# VIC20_SExpII.net
KiCad netlist of a schematic drawn in EAGLE
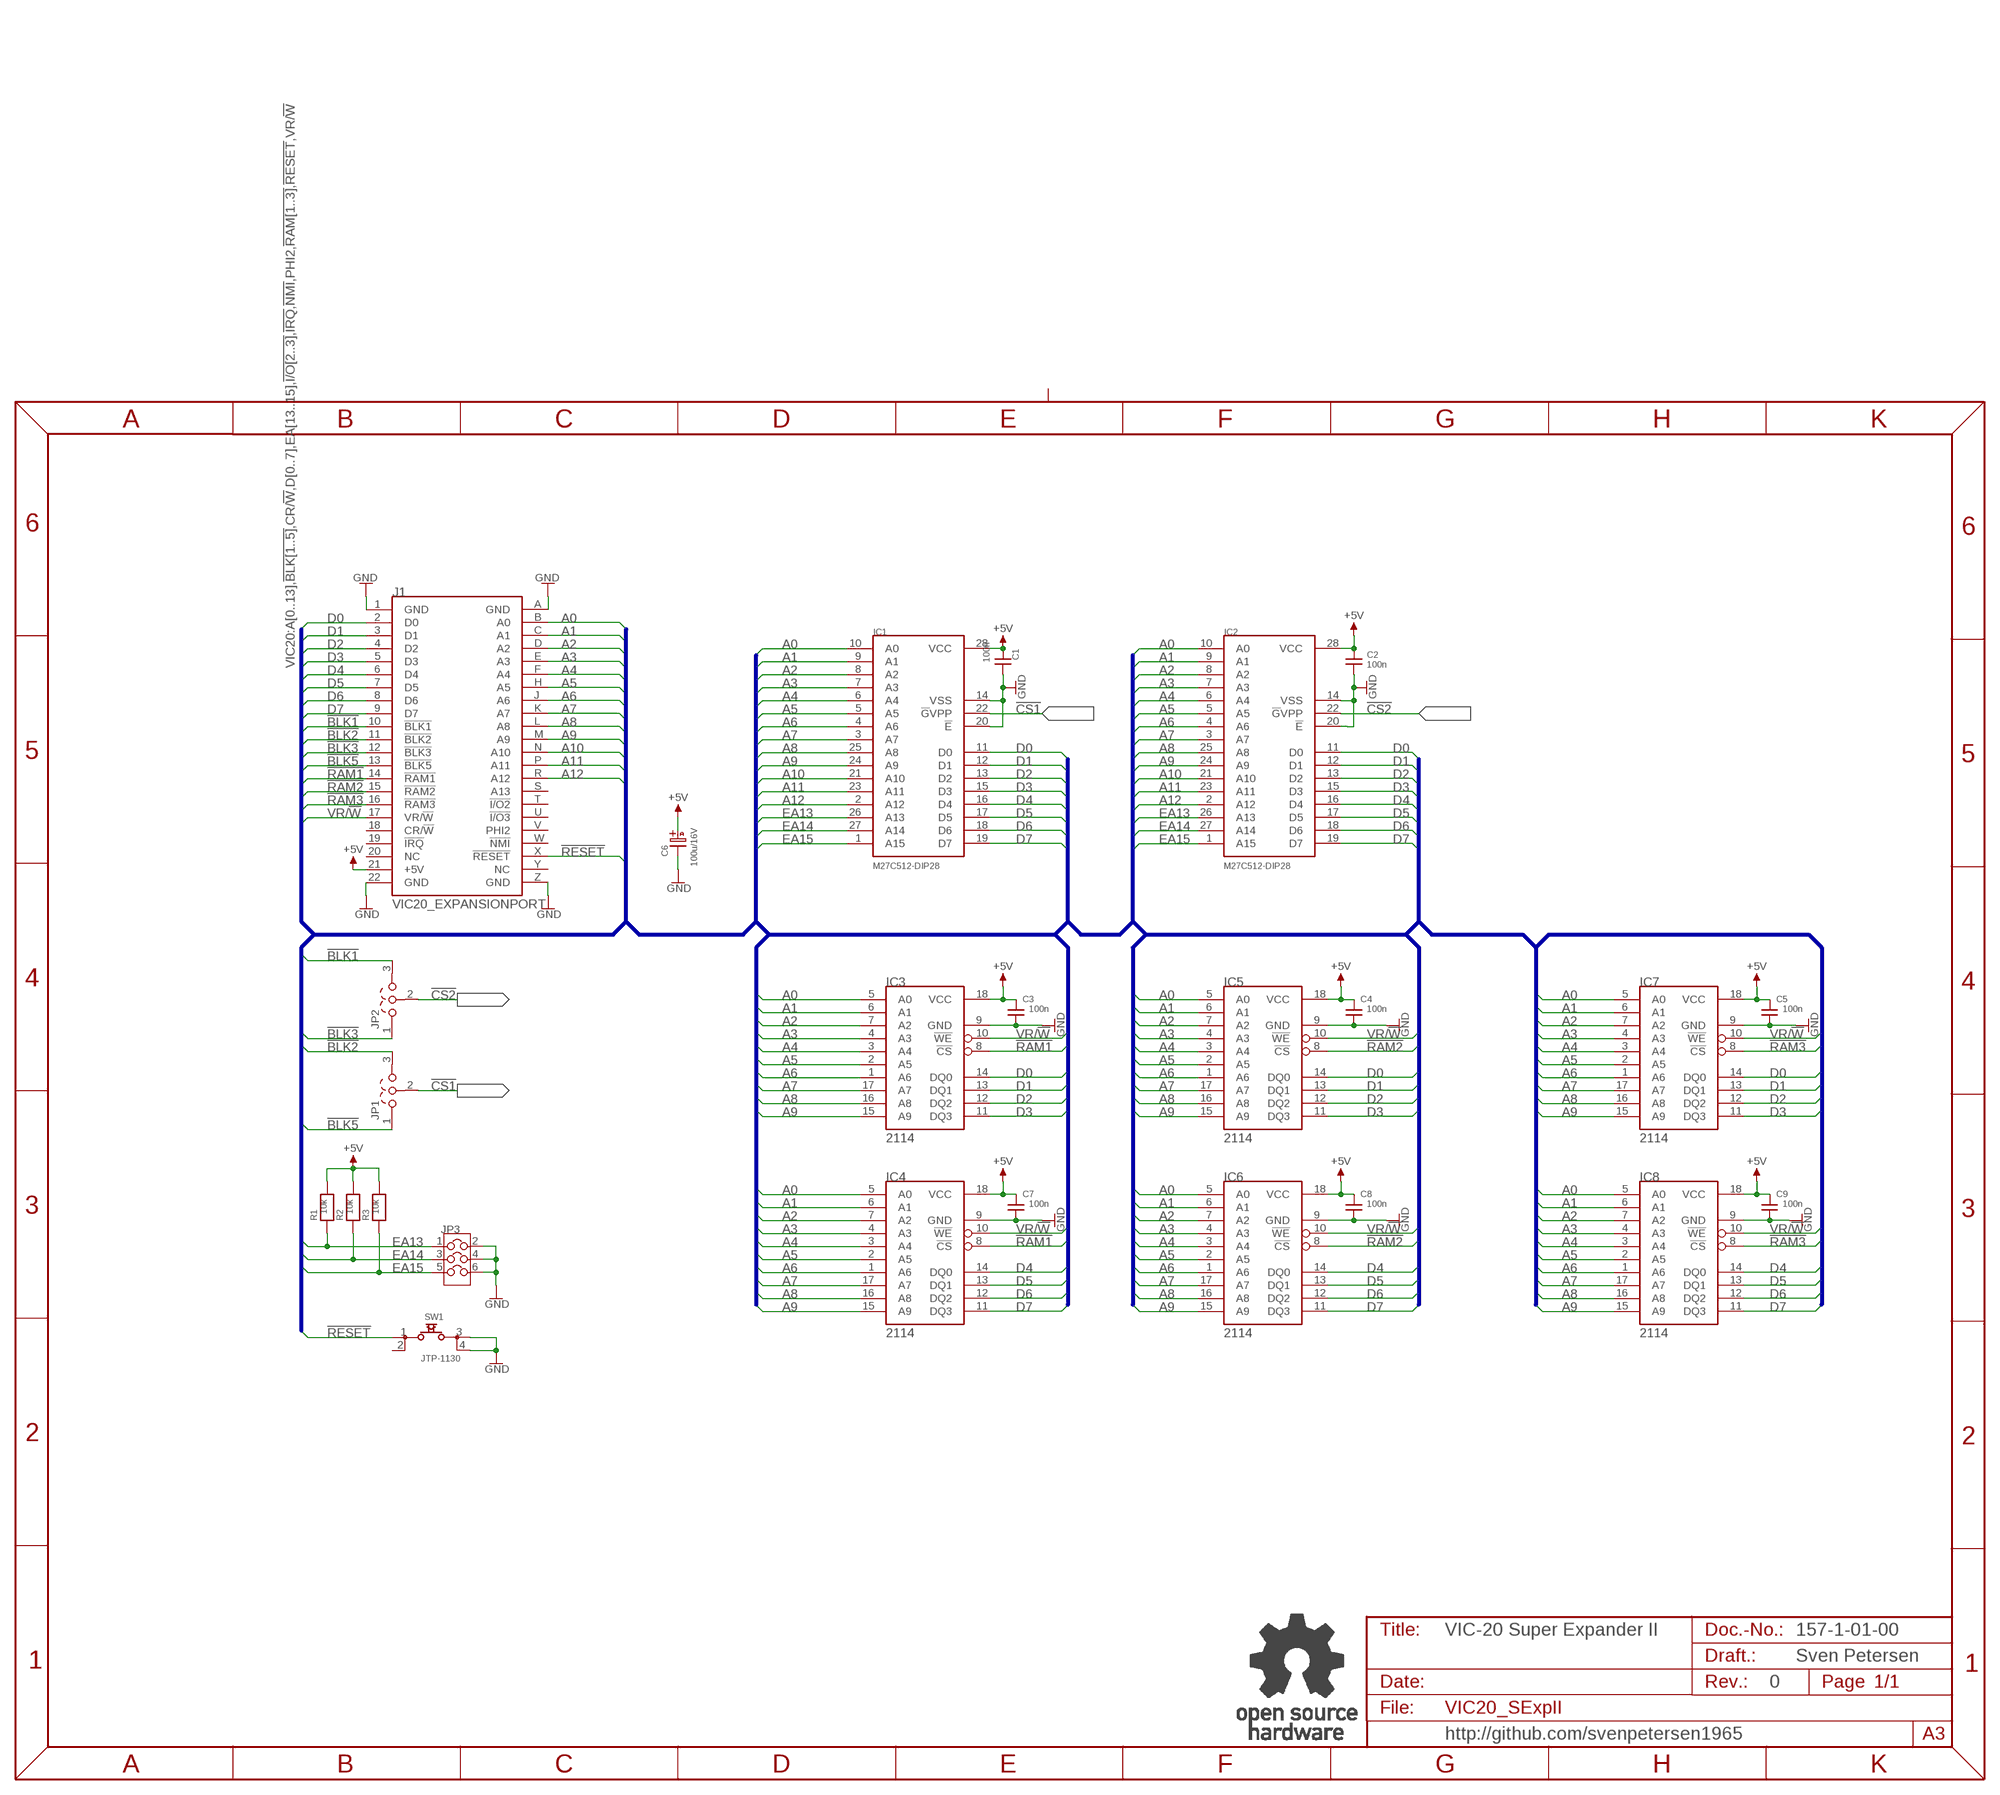
[diagram p0: schematic, sheet 1]

(export (version "E")
  (design (tool "Eeschema 10.0.6"))
  (components
    (comp (ref "C1")
      (value "100n")
      (footprint "eagle-import:C-2,5")
      (libsource (lib "eagle-import") (part "CAP01"))
    )
    (comp (ref "C2")
      (value "100n")
      (footprint "eagle-import:C-2,5")
      (libsource (lib "eagle-import") (part "CAP01"))
    )
    (comp (ref "C3")
      (value "100n")
      (footprint "eagle-import:C-2,5")
      (libsource (lib "eagle-import") (part "CAP01"))
    )
    (comp (ref "C4")
      (value "100n")
      (footprint "eagle-import:C-2,5")
      (libsource (lib "eagle-import") (part "CAP01"))
    )
    (comp (ref "C5")
      (value "100n")
      (footprint "eagle-import:C-2,5")
      (libsource (lib "eagle-import") (part "CAP01"))
    )
    (comp (ref "C6")
      (value "100u/16V")
      (footprint "eagle-import:C07_2,5")
      (libsource (lib "eagle-import") (part "C07/2,5"))
    )
    (comp (ref "C7")
      (value "100n")
      (footprint "eagle-import:C-2,5")
      (libsource (lib "eagle-import") (part "CAP01"))
    )
    (comp (ref "C8")
      (value "100n")
      (footprint "eagle-import:C-2,5")
      (libsource (lib "eagle-import") (part "CAP01"))
    )
    (comp (ref "C9")
      (value "100n")
      (footprint "eagle-import:C-2,5")
      (libsource (lib "eagle-import") (part "CAP01"))
    )
    (comp (ref "IC1")
      (value "M27C512-DIP28")
      (footprint "eagle-import:DIL28-6")
      (libsource (lib "eagle-import") (part "M27C512-DIP28"))
    )
    (comp (ref "IC2")
      (value "M27C512-DIP28")
      (footprint "eagle-import:DIL28-6")
      (libsource (lib "eagle-import") (part "M27C512-DIP28"))
    )
    (comp (ref "IC3")
      (value "2114")
      (footprint "eagle-import:DIL18")
      (libsource (lib "eagle-import") (part "2114"))
    )
    (comp (ref "IC4")
      (value "2114")
      (footprint "eagle-import:DIL18")
      (libsource (lib "eagle-import") (part "2114"))
    )
    (comp (ref "IC5")
      (value "2114")
      (footprint "eagle-import:DIL18")
      (libsource (lib "eagle-import") (part "2114"))
    )
    (comp (ref "IC6")
      (value "2114")
      (footprint "eagle-import:DIL18")
      (libsource (lib "eagle-import") (part "2114"))
    )
    (comp (ref "IC7")
      (value "2114")
      (footprint "eagle-import:DIL18")
      (libsource (lib "eagle-import") (part "2114"))
    )
    (comp (ref "IC8")
      (value "2114")
      (footprint "eagle-import:DIL18")
      (libsource (lib "eagle-import") (part "2114"))
    )
    (comp (ref "J1")
      (value "VIC20_EXPANSIONPORT")
      (footprint "eagle-import:VIC20_EXPANSION")
      (libsource (lib "eagle-import") (part "VIC20_EXPANSIONPORT"))
    )
    (comp (ref "JP1")
      (value "COMBI-3P")
      (footprint "eagle-import:COMBI-3P")
      (libsource (lib "eagle-import") (part "COMBI-3P"))
    )
    (comp (ref "JP2")
      (value "COMBI-3P")
      (footprint "eagle-import:COMBI-3P")
      (libsource (lib "eagle-import") (part "COMBI-3P"))
    )
    (comp (ref "JP3")
      (value "COMBI-3X2P")
      (footprint "eagle-import:COMBI-3X2")
      (libsource (lib "eagle-import") (part "COMBI-3X2P"))
    )
    (comp (ref "R1")
      (value "10k")
      (footprint "eagle-import:R-10")
      (libsource (lib "eagle-import") (part "RES04"))
    )
    (comp (ref "R2")
      (value "10k")
      (footprint "eagle-import:R-10")
      (libsource (lib "eagle-import") (part "RES04"))
    )
    (comp (ref "R3")
      (value "10k")
      (footprint "eagle-import:R-10")
      (libsource (lib "eagle-import") (part "RES04"))
    )
    (comp (ref "SW1")
      (value "JTP-1130")
      (footprint "eagle-import:JTP-1130")
      (libsource (lib "eagle-import") (part "JTP-1130"))
    )
    (comp (ref "U$2")
      (value "OPEN_SOURCE_HW")
      (footprint "eagle-import:OPENHW")
      (libsource (lib "eagle-import") (part "OPEN_SOURCE_HW"))
    )
  )
  (nets
    (net (code "5") (name "+5V") (class "Default")
      (node (ref "C1") (pin "1") (pinfunction "1_1") (pintype "passive"))
      (node (ref "C2") (pin "1") (pinfunction "1_1") (pintype "passive"))
      (node (ref "C3") (pin "2") (pinfunction "2_2") (pintype "passive"))
      (node (ref "C4") (pin "2") (pinfunction "2_2") (pintype "passive"))
      (node (ref "C5") (pin "2") (pinfunction "2_2") (pintype "passive"))
      (node (ref "C6") (pin "A") (pinfunction "+_A") (pintype "passive"))
      (node (ref "C7") (pin "2") (pinfunction "2_2") (pintype "passive"))
      (node (ref "C8") (pin "2") (pinfunction "2_2") (pintype "passive"))
      (node (ref "C9") (pin "2") (pinfunction "2_2") (pintype "passive"))
      (node (ref "IC1") (pin "28") (pinfunction "VCC_28") (pintype "power_in"))
      (node (ref "IC2") (pin "28") (pinfunction "VCC_28") (pintype "power_in"))
      (node (ref "IC3") (pin "18") (pinfunction "VCC_18") (pintype "power_in"))
      (node (ref "IC4") (pin "18") (pinfunction "VCC_18") (pintype "power_in"))
      (node (ref "IC5") (pin "18") (pinfunction "VCC_18") (pintype "power_in"))
      (node (ref "IC6") (pin "18") (pinfunction "VCC_18") (pintype "power_in"))
      (node (ref "IC7") (pin "18") (pinfunction "VCC_18") (pintype "power_in"))
      (node (ref "IC8") (pin "18") (pinfunction "VCC_18") (pintype "power_in"))
      (node (ref "J1") (pin "21") (pinfunction "+5V_21") (pintype "power_in"))
      (node (ref "R1") (pin "2") (pinfunction "2_2") (pintype "passive"))
      (node (ref "R2") (pin "2") (pinfunction "2_2") (pintype "passive"))
      (node (ref "R3") (pin "2") (pinfunction "2_2") (pintype "passive"))
    )
    (net (code "6") (name "/A0") (class "Default")
      (node (ref "IC1") (pin "10") (pinfunction "A0_10") (pintype "input"))
      (node (ref "IC2") (pin "10") (pinfunction "A0_10") (pintype "input"))
      (node (ref "IC3") (pin "5") (pinfunction "A0_5") (pintype "input"))
      (node (ref "IC4") (pin "5") (pinfunction "A0_5") (pintype "input"))
      (node (ref "IC5") (pin "5") (pinfunction "A0_5") (pintype "input"))
      (node (ref "IC6") (pin "5") (pinfunction "A0_5") (pintype "input"))
      (node (ref "IC7") (pin "5") (pinfunction "A0_5") (pintype "input"))
      (node (ref "IC8") (pin "5") (pinfunction "A0_5") (pintype "input"))
      (node (ref "J1") (pin "B") (pinfunction "A0_B") (pintype "bidirectional"))
    )
    (net (code "7") (name "/A1") (class "Default")
      (node (ref "IC1") (pin "9") (pinfunction "A1_9") (pintype "input"))
      (node (ref "IC2") (pin "9") (pinfunction "A1_9") (pintype "input"))
      (node (ref "IC3") (pin "6") (pinfunction "A1_6") (pintype "input"))
      (node (ref "IC4") (pin "6") (pinfunction "A1_6") (pintype "input"))
      (node (ref "IC5") (pin "6") (pinfunction "A1_6") (pintype "input"))
      (node (ref "IC6") (pin "6") (pinfunction "A1_6") (pintype "input"))
      (node (ref "IC7") (pin "6") (pinfunction "A1_6") (pintype "input"))
      (node (ref "IC8") (pin "6") (pinfunction "A1_6") (pintype "input"))
      (node (ref "J1") (pin "C") (pinfunction "A1_C") (pintype "bidirectional"))
    )
    (net (code "8") (name "/A2") (class "Default")
      (node (ref "IC1") (pin "8") (pinfunction "A2_8") (pintype "input"))
      (node (ref "IC2") (pin "8") (pinfunction "A2_8") (pintype "input"))
      (node (ref "IC3") (pin "7") (pinfunction "A2_7") (pintype "input"))
      (node (ref "IC4") (pin "7") (pinfunction "A2_7") (pintype "input"))
      (node (ref "IC5") (pin "7") (pinfunction "A2_7") (pintype "input"))
      (node (ref "IC6") (pin "7") (pinfunction "A2_7") (pintype "input"))
      (node (ref "IC7") (pin "7") (pinfunction "A2_7") (pintype "input"))
      (node (ref "IC8") (pin "7") (pinfunction "A2_7") (pintype "input"))
      (node (ref "J1") (pin "D") (pinfunction "A2_D") (pintype "bidirectional"))
    )
    (net (code "9") (name "/A3") (class "Default")
      (node (ref "IC1") (pin "7") (pinfunction "A3_7") (pintype "input"))
      (node (ref "IC2") (pin "7") (pinfunction "A3_7") (pintype "input"))
      (node (ref "IC3") (pin "4") (pinfunction "A3_4") (pintype "input"))
      (node (ref "IC4") (pin "4") (pinfunction "A3_4") (pintype "input"))
      (node (ref "IC5") (pin "4") (pinfunction "A3_4") (pintype "input"))
      (node (ref "IC6") (pin "4") (pinfunction "A3_4") (pintype "input"))
      (node (ref "IC7") (pin "4") (pinfunction "A3_4") (pintype "input"))
      (node (ref "IC8") (pin "4") (pinfunction "A3_4") (pintype "input"))
      (node (ref "J1") (pin "E") (pinfunction "A3_E") (pintype "bidirectional"))
    )
    (net (code "10") (name "/A4") (class "Default")
      (node (ref "IC1") (pin "6") (pinfunction "A4_6") (pintype "input"))
      (node (ref "IC2") (pin "6") (pinfunction "A4_6") (pintype "input"))
      (node (ref "IC3") (pin "3") (pinfunction "A4_3") (pintype "input"))
      (node (ref "IC4") (pin "3") (pinfunction "A4_3") (pintype "input"))
      (node (ref "IC5") (pin "3") (pinfunction "A4_3") (pintype "input"))
      (node (ref "IC6") (pin "3") (pinfunction "A4_3") (pintype "input"))
      (node (ref "IC7") (pin "3") (pinfunction "A4_3") (pintype "input"))
      (node (ref "IC8") (pin "3") (pinfunction "A4_3") (pintype "input"))
      (node (ref "J1") (pin "F") (pinfunction "A4_F") (pintype "bidirectional"))
    )
    (net (code "11") (name "/A5") (class "Default")
      (node (ref "IC1") (pin "5") (pinfunction "A5_5") (pintype "input"))
      (node (ref "IC2") (pin "5") (pinfunction "A5_5") (pintype "input"))
      (node (ref "IC3") (pin "2") (pinfunction "A5_2") (pintype "input"))
      (node (ref "IC4") (pin "2") (pinfunction "A5_2") (pintype "input"))
      (node (ref "IC5") (pin "2") (pinfunction "A5_2") (pintype "input"))
      (node (ref "IC6") (pin "2") (pinfunction "A5_2") (pintype "input"))
      (node (ref "IC7") (pin "2") (pinfunction "A5_2") (pintype "input"))
      (node (ref "IC8") (pin "2") (pinfunction "A5_2") (pintype "input"))
      (node (ref "J1") (pin "H") (pinfunction "A5_H") (pintype "bidirectional"))
    )
    (net (code "12") (name "/A6") (class "Default")
      (node (ref "IC1") (pin "4") (pinfunction "A6_4") (pintype "input"))
      (node (ref "IC2") (pin "4") (pinfunction "A6_4") (pintype "input"))
      (node (ref "IC3") (pin "1") (pinfunction "A6_1") (pintype "input"))
      (node (ref "IC4") (pin "1") (pinfunction "A6_1") (pintype "input"))
      (node (ref "IC5") (pin "1") (pinfunction "A6_1") (pintype "input"))
      (node (ref "IC6") (pin "1") (pinfunction "A6_1") (pintype "input"))
      (node (ref "IC7") (pin "1") (pinfunction "A6_1") (pintype "input"))
      (node (ref "IC8") (pin "1") (pinfunction "A6_1") (pintype "input"))
      (node (ref "J1") (pin "J") (pinfunction "A6_J") (pintype "bidirectional"))
    )
    (net (code "13") (name "/A7") (class "Default")
      (node (ref "IC1") (pin "3") (pinfunction "A7_3") (pintype "input"))
      (node (ref "IC2") (pin "3") (pinfunction "A7_3") (pintype "input"))
      (node (ref "IC3") (pin "17") (pinfunction "A7_17") (pintype "input"))
      (node (ref "IC4") (pin "17") (pinfunction "A7_17") (pintype "input"))
      (node (ref "IC5") (pin "17") (pinfunction "A7_17") (pintype "input"))
      (node (ref "IC6") (pin "17") (pinfunction "A7_17") (pintype "input"))
      (node (ref "IC7") (pin "17") (pinfunction "A7_17") (pintype "input"))
      (node (ref "IC8") (pin "17") (pinfunction "A7_17") (pintype "input"))
      (node (ref "J1") (pin "K") (pinfunction "A7_K") (pintype "bidirectional"))
    )
    (net (code "14") (name "/A8") (class "Default")
      (node (ref "IC1") (pin "25") (pinfunction "A8_25") (pintype "input"))
      (node (ref "IC2") (pin "25") (pinfunction "A8_25") (pintype "input"))
      (node (ref "IC3") (pin "16") (pinfunction "A8_16") (pintype "input"))
      (node (ref "IC4") (pin "16") (pinfunction "A8_16") (pintype "input"))
      (node (ref "IC5") (pin "16") (pinfunction "A8_16") (pintype "input"))
      (node (ref "IC6") (pin "16") (pinfunction "A8_16") (pintype "input"))
      (node (ref "IC7") (pin "16") (pinfunction "A8_16") (pintype "input"))
      (node (ref "IC8") (pin "16") (pinfunction "A8_16") (pintype "input"))
      (node (ref "J1") (pin "L") (pinfunction "A8_L") (pintype "bidirectional"))
    )
    (net (code "15") (name "/A9") (class "Default")
      (node (ref "IC1") (pin "24") (pinfunction "A9_24") (pintype "input"))
      (node (ref "IC2") (pin "24") (pinfunction "A9_24") (pintype "input"))
      (node (ref "IC3") (pin "15") (pinfunction "A9_15") (pintype "input"))
      (node (ref "IC4") (pin "15") (pinfunction "A9_15") (pintype "input"))
      (node (ref "IC5") (pin "15") (pinfunction "A9_15") (pintype "input"))
      (node (ref "IC6") (pin "15") (pinfunction "A9_15") (pintype "input"))
      (node (ref "IC7") (pin "15") (pinfunction "A9_15") (pintype "input"))
      (node (ref "IC8") (pin "15") (pinfunction "A9_15") (pintype "input"))
      (node (ref "J1") (pin "M") (pinfunction "A9_M") (pintype "bidirectional"))
    )
    (net (code "16") (name "/A10") (class "Default")
      (node (ref "IC1") (pin "21") (pinfunction "A10_21") (pintype "input"))
      (node (ref "IC2") (pin "21") (pinfunction "A10_21") (pintype "input"))
      (node (ref "J1") (pin "N") (pinfunction "A10_N") (pintype "bidirectional"))
    )
    (net (code "17") (name "/A11") (class "Default")
      (node (ref "IC1") (pin "23") (pinfunction "A11_23") (pintype "input"))
      (node (ref "IC2") (pin "23") (pinfunction "A11_23") (pintype "input"))
      (node (ref "J1") (pin "P") (pinfunction "A11_P") (pintype "bidirectional"))
    )
    (net (code "18") (name "/A12") (class "Default")
      (node (ref "IC1") (pin "2") (pinfunction "A12_2") (pintype "input"))
      (node (ref "IC2") (pin "2") (pinfunction "A12_2") (pintype "input"))
      (node (ref "J1") (pin "R") (pinfunction "A12_R") (pintype "bidirectional"))
    )
    (net (code "19") (name "/D0") (class "Default")
      (node (ref "IC1") (pin "11") (pinfunction "D0_11") (pintype "bidirectional"))
      (node (ref "IC2") (pin "11") (pinfunction "D0_11") (pintype "bidirectional"))
      (node (ref "IC3") (pin "14") (pinfunction "DQ0_14") (pintype "bidirectional"))
      (node (ref "IC5") (pin "14") (pinfunction "DQ0_14") (pintype "bidirectional"))
      (node (ref "IC7") (pin "14") (pinfunction "DQ0_14") (pintype "bidirectional"))
      (node (ref "J1") (pin "2") (pinfunction "D0_2") (pintype "bidirectional"))
    )
    (net (code "20") (name "/D1") (class "Default")
      (node (ref "IC1") (pin "12") (pinfunction "D1_12") (pintype "bidirectional"))
      (node (ref "IC2") (pin "12") (pinfunction "D1_12") (pintype "bidirectional"))
      (node (ref "IC3") (pin "13") (pinfunction "DQ1_13") (pintype "bidirectional"))
      (node (ref "IC5") (pin "13") (pinfunction "DQ1_13") (pintype "bidirectional"))
      (node (ref "IC7") (pin "13") (pinfunction "DQ1_13") (pintype "bidirectional"))
      (node (ref "J1") (pin "3") (pinfunction "D1_3") (pintype "bidirectional"))
    )
    (net (code "21") (name "/D2") (class "Default")
      (node (ref "IC1") (pin "13") (pinfunction "D2_13") (pintype "bidirectional"))
      (node (ref "IC2") (pin "13") (pinfunction "D2_13") (pintype "bidirectional"))
      (node (ref "IC3") (pin "12") (pinfunction "DQ2_12") (pintype "bidirectional"))
      (node (ref "IC5") (pin "12") (pinfunction "DQ2_12") (pintype "bidirectional"))
      (node (ref "IC7") (pin "12") (pinfunction "DQ2_12") (pintype "bidirectional"))
      (node (ref "J1") (pin "4") (pinfunction "D2_4") (pintype "bidirectional"))
    )
    (net (code "22") (name "/D3") (class "Default")
      (node (ref "IC1") (pin "15") (pinfunction "D3_15") (pintype "bidirectional"))
      (node (ref "IC2") (pin "15") (pinfunction "D3_15") (pintype "bidirectional"))
      (node (ref "IC3") (pin "11") (pinfunction "DQ3_11") (pintype "bidirectional"))
      (node (ref "IC5") (pin "11") (pinfunction "DQ3_11") (pintype "bidirectional"))
      (node (ref "IC7") (pin "11") (pinfunction "DQ3_11") (pintype "bidirectional"))
      (node (ref "J1") (pin "5") (pinfunction "D3_5") (pintype "bidirectional"))
    )
    (net (code "23") (name "/D4") (class "Default")
      (node (ref "IC1") (pin "16") (pinfunction "D4_16") (pintype "bidirectional"))
      (node (ref "IC2") (pin "16") (pinfunction "D4_16") (pintype "bidirectional"))
      (node (ref "IC4") (pin "14") (pinfunction "DQ0_14") (pintype "bidirectional"))
      (node (ref "IC6") (pin "14") (pinfunction "DQ0_14") (pintype "bidirectional"))
      (node (ref "IC8") (pin "14") (pinfunction "DQ0_14") (pintype "bidirectional"))
      (node (ref "J1") (pin "6") (pinfunction "D4_6") (pintype "bidirectional"))
    )
    (net (code "24") (name "/D5") (class "Default")
      (node (ref "IC1") (pin "17") (pinfunction "D5_17") (pintype "bidirectional"))
      (node (ref "IC2") (pin "17") (pinfunction "D5_17") (pintype "bidirectional"))
      (node (ref "IC4") (pin "13") (pinfunction "DQ1_13") (pintype "bidirectional"))
      (node (ref "IC6") (pin "13") (pinfunction "DQ1_13") (pintype "bidirectional"))
      (node (ref "IC8") (pin "13") (pinfunction "DQ1_13") (pintype "bidirectional"))
      (node (ref "J1") (pin "7") (pinfunction "D5_7") (pintype "bidirectional"))
    )
    (net (code "25") (name "/D6") (class "Default")
      (node (ref "IC1") (pin "18") (pinfunction "D6_18") (pintype "bidirectional"))
      (node (ref "IC2") (pin "18") (pinfunction "D6_18") (pintype "bidirectional"))
      (node (ref "IC4") (pin "12") (pinfunction "DQ2_12") (pintype "bidirectional"))
      (node (ref "IC6") (pin "12") (pinfunction "DQ2_12") (pintype "bidirectional"))
      (node (ref "IC8") (pin "12") (pinfunction "DQ2_12") (pintype "bidirectional"))
      (node (ref "J1") (pin "8") (pinfunction "D6_8") (pintype "bidirectional"))
    )
    (net (code "26") (name "/D7") (class "Default")
      (node (ref "IC1") (pin "19") (pinfunction "D7_19") (pintype "bidirectional"))
      (node (ref "IC2") (pin "19") (pinfunction "D7_19") (pintype "bidirectional"))
      (node (ref "IC4") (pin "11") (pinfunction "DQ3_11") (pintype "bidirectional"))
      (node (ref "IC6") (pin "11") (pinfunction "DQ3_11") (pintype "bidirectional"))
      (node (ref "IC8") (pin "11") (pinfunction "DQ3_11") (pintype "bidirectional"))
      (node (ref "J1") (pin "9") (pinfunction "D7_9") (pintype "bidirectional"))
    )
    (net (code "27") (name "/EA13") (class "Default")
      (node (ref "IC1") (pin "26") (pinfunction "A13_26") (pintype "input"))
      (node (ref "IC2") (pin "26") (pinfunction "A13_26") (pintype "input"))
      (node (ref "JP3") (pin "1") (pinfunction "1_1") (pintype "bidirectional"))
      (node (ref "R1") (pin "1") (pinfunction "1_1") (pintype "passive"))
    )
    (net (code "28") (name "/EA14") (class "Default")
      (node (ref "IC1") (pin "27") (pinfunction "A14_27") (pintype "input"))
      (node (ref "IC2") (pin "27") (pinfunction "A14_27") (pintype "input"))
      (node (ref "JP3") (pin "3") (pinfunction "3_3") (pintype "bidirectional"))
      (node (ref "R2") (pin "1") (pinfunction "1_1") (pintype "passive"))
    )
    (net (code "29") (name "/EA15") (class "Default")
      (node (ref "IC1") (pin "1") (pinfunction "A15_1") (pintype "input"))
      (node (ref "IC2") (pin "1") (pinfunction "A15_1") (pintype "input"))
      (node (ref "JP3") (pin "5") (pinfunction "5_5") (pintype "bidirectional"))
      (node (ref "R3") (pin "1") (pinfunction "1_1") (pintype "passive"))
    )
    (net (code "30") (name "/NC") (class "Default")
      (node (ref "J1") (pin "20") (pinfunction "NC_20") (pintype "power_in"))
    )
    (net (code "31") (name "/VR{slash}~{W}") (class "Default")
      (node (ref "IC3") (pin "10") (pinfunction "~{WE}_10") (pintype "input"))
      (node (ref "IC4") (pin "10") (pinfunction "~{WE}_10") (pintype "input"))
      (node (ref "IC5") (pin "10") (pinfunction "~{WE}_10") (pintype "input"))
      (node (ref "IC6") (pin "10") (pinfunction "~{WE}_10") (pintype "input"))
      (node (ref "IC7") (pin "10") (pinfunction "~{WE}_10") (pintype "input"))
      (node (ref "IC8") (pin "10") (pinfunction "~{WE}_10") (pintype "input"))
      (node (ref "J1") (pin "17") (pinfunction "VR/~{W}_17") (pintype "output"))
    )
    (net (code "33") (name "/~{BLK1}") (class "Default")
      (node (ref "J1") (pin "10") (pinfunction "~{BLK1}_10") (pintype "input"))
      (node (ref "JP2") (pin "3") (pinfunction "3_3") (pintype "bidirectional"))
    )
    (net (code "34") (name "/~{BLK2}") (class "Default")
      (node (ref "J1") (pin "11") (pinfunction "~{BLK2}_11") (pintype "input"))
      (node (ref "JP1") (pin "3") (pinfunction "3_3") (pintype "bidirectional"))
    )
    (net (code "35") (name "/~{BLK3}") (class "Default")
      (node (ref "J1") (pin "12") (pinfunction "~{BLK3}_12") (pintype "output"))
      (node (ref "JP2") (pin "1") (pinfunction "1_1") (pintype "bidirectional"))
    )
    (net (code "36") (name "/~{BLK5}") (class "Default")
      (node (ref "J1") (pin "13") (pinfunction "~{BLK5}_13") (pintype "output"))
      (node (ref "JP1") (pin "1") (pinfunction "1_1") (pintype "bidirectional"))
    )
    (net (code "37") (name "/~{CS1}") (class "Default")
      (node (ref "IC1") (pin "22") (pinfunction "~{G}VPP_22") (pintype "input"))
      (node (ref "JP1") (pin "2") (pinfunction "2_2") (pintype "bidirectional"))
    )
    (net (code "38") (name "/~{CS2}") (class "Default")
      (node (ref "IC2") (pin "22") (pinfunction "~{G}VPP_22") (pintype "input"))
      (node (ref "JP2") (pin "2") (pinfunction "2_2") (pintype "bidirectional"))
    )
    (net (code "39") (name "/~{RAM1}") (class "Default")
      (node (ref "IC3") (pin "8") (pinfunction "~{CS}_8") (pintype "input"))
      (node (ref "IC4") (pin "8") (pinfunction "~{CS}_8") (pintype "input"))
      (node (ref "J1") (pin "14") (pinfunction "~{RAM1}_14") (pintype "input"))
    )
    (net (code "40") (name "/~{RAM2}") (class "Default")
      (node (ref "IC5") (pin "8") (pinfunction "~{CS}_8") (pintype "input"))
      (node (ref "IC6") (pin "8") (pinfunction "~{CS}_8") (pintype "input"))
      (node (ref "J1") (pin "15") (pinfunction "~{RAM2}_15") (pintype "output"))
    )
    (net (code "41") (name "/~{RAM3}") (class "Default")
      (node (ref "IC7") (pin "8") (pinfunction "~{CS}_8") (pintype "input"))
      (node (ref "IC8") (pin "8") (pinfunction "~{CS}_8") (pintype "input"))
      (node (ref "J1") (pin "16") (pinfunction "~{RAM3}_16") (pintype "output"))
    )
    (net (code "42") (name "/~{RESET}") (class "Default")
      (node (ref "J1") (pin "X") (pinfunction "~{RESET}_X") (pintype "open_collector"))
      (node (ref "SW1") (pin "1") (pinfunction "1_1") (pintype "passive"))
    )
    (net (code "43") (name "GND") (class "Default")
      (node (ref "C1") (pin "2") (pinfunction "2_2") (pintype "passive"))
      (node (ref "C2") (pin "2") (pinfunction "2_2") (pintype "passive"))
      (node (ref "C3") (pin "1") (pinfunction "1_1") (pintype "passive"))
      (node (ref "C4") (pin "1") (pinfunction "1_1") (pintype "passive"))
      (node (ref "C5") (pin "1") (pinfunction "1_1") (pintype "passive"))
      (node (ref "C6") (pin "K") (pinfunction "-_K") (pintype "passive"))
      (node (ref "C7") (pin "1") (pinfunction "1_1") (pintype "passive"))
      (node (ref "C8") (pin "1") (pinfunction "1_1") (pintype "passive"))
      (node (ref "C9") (pin "1") (pinfunction "1_1") (pintype "passive"))
      (node (ref "IC1") (pin "14") (pinfunction "VSS_14") (pintype "power_in"))
      (node (ref "IC1") (pin "20") (pinfunction "~{E}_20") (pintype "input"))
      (node (ref "IC2") (pin "14") (pinfunction "VSS_14") (pintype "power_in"))
      (node (ref "IC2") (pin "20") (pinfunction "~{E}_20") (pintype "input"))
      (node (ref "IC3") (pin "9") (pinfunction "GND_9") (pintype "power_in"))
      (node (ref "IC4") (pin "9") (pinfunction "GND_9") (pintype "power_in"))
      (node (ref "IC5") (pin "9") (pinfunction "GND_9") (pintype "power_in"))
      (node (ref "IC6") (pin "9") (pinfunction "GND_9") (pintype "power_in"))
      (node (ref "IC7") (pin "9") (pinfunction "GND_9") (pintype "power_in"))
      (node (ref "IC8") (pin "9") (pinfunction "GND_9") (pintype "power_in"))
      (node (ref "J1") (pin "1") (pinfunction "GND_1") (pintype "power_in"))
      (node (ref "J1") (pin "22") (pinfunction "GND_22") (pintype "power_in"))
      (node (ref "J1") (pin "A") (pinfunction "GND_A") (pintype "power_in"))
      (node (ref "J1") (pin "Z") (pinfunction "GND_Z") (pintype "power_in"))
      (node (ref "JP3") (pin "2") (pinfunction "2_2") (pintype "bidirectional"))
      (node (ref "JP3") (pin "4") (pinfunction "4_4") (pintype "bidirectional"))
      (node (ref "JP3") (pin "6") (pinfunction "6_6") (pintype "bidirectional"))
      (node (ref "SW1") (pin "3") (pinfunction "3_3") (pintype "passive"))
      (node (ref "SW1") (pin "4") (pinfunction "4_4") (pintype "passive"))
    )
    (net (code "44") (name "unconnected-(J1-A13-PadS)") (class "Default")
      (node (ref "J1") (pin "S") (pinfunction "A13_S") (pintype "bidirectional"))
    )
    (net (code "45") (name "unconnected-(J1-CR{slash}~{W}-Pad18)") (class "Default")
      (node (ref "J1") (pin "18") (pinfunction "CR/~{W}_18") (pintype "output"))
    )
    (net (code "46") (name "unconnected-(J1-NC-PadY)") (class "Default")
      (node (ref "J1") (pin "Y") (pinfunction "NC_Y") (pintype "bidirectional"))
    )
    (net (code "47") (name "unconnected-(J1-PHI2-PadV)") (class "Default")
      (node (ref "J1") (pin "V") (pinfunction "PHI2_V") (pintype "bidirectional"))
    )
    (net (code "48") (name "unconnected-(J1-~{IRQ}-Pad19)") (class "Default")
      (node (ref "J1") (pin "19") (pinfunction "~{IRQ}_19") (pintype "input"))
    )
    (net (code "49") (name "unconnected-(J1-~{I{slash}O2}-PadT)") (class "Default")
      (node (ref "J1") (pin "T") (pinfunction "~{I/O2}_T") (pintype "output"))
    )
    (net (code "50") (name "unconnected-(J1-~{I{slash}O3}-PadU)") (class "Default")
      (node (ref "J1") (pin "U") (pinfunction "~{I/O3}_U") (pintype "output"))
    )
    (net (code "51") (name "unconnected-(J1-~{NMI}-PadW)") (class "Default")
      (node (ref "J1") (pin "W") (pinfunction "~{NMI}_W") (pintype "input"))
    )
    (net (code "52") (name "unconnected-(SW1-Pad2)") (class "Default")
      (node (ref "SW1") (pin "2") (pinfunction "2_2") (pintype "passive"))
    )
  )
)
